# LEDS.net
KiCad netlist of a schematic drawn in Altium Designer
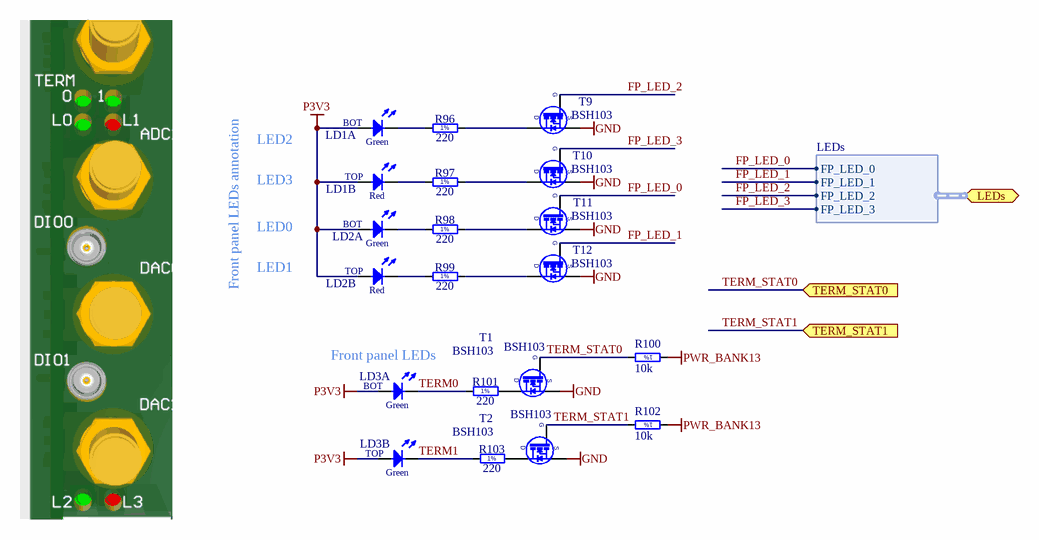
[diagram p0: LEDS.SchDoc]

(export (version "E")
  (design (tool "Eeschema 10.0.6"))
  (components
    (comp (ref "LD1")
      (value "Red/Green")
      (footprint "LED_DIALIGHT_571-0112F")
      (description "2x LED  Botom Green, Top Red")
      (fields
        (field (name "PART NUMBER") "LED_DIALIGHT_571-0112F")
        (field (name "MANUFACTURER") "DIALIGHT")
        (field (name "AUTHOR") "CERN DEM JLC")
      )
      (libsource (lib "ICs And Semiconductors") (part "LED x2 G-1C2A-BOT_R-3C4A-TOP"))
    )
    (comp (ref "LD2")
      (value "Red/Green")
      (footprint "LED_DIALIGHT_571-0112F")
      (description "2x LED  Botom Green, Top Red")
      (fields
        (field (name "PART NUMBER") "LED_DIALIGHT_571-0112F")
        (field (name "MANUFACTURER") "DIALIGHT")
        (field (name "AUTHOR") "CERN DEM JLC")
      )
      (libsource (lib "ICs And Semiconductors") (part "LED x2 G-1C2A-BOT_R-3C4A-TOP"))
    )
    (comp (ref "LD3")
      (value "Green/Green")
      (footprint "LED_DIALIGHT_571-0122F")
      (description "LED x2 Green 1C2A-BOT_3C4A-TOP")
      (fields
        (field (name "PART NUMBER") "LED_DIALIGHT_571-0122F")
        (field (name "MANUFACTURER") "DIALIGHT")
        (field (name "AUTHOR") "CERN DEM JLC")
      )
      (libsource (lib "ICs And Semiconductors") (part "LED x2 Green 1C2A-BOT_3C4A-TOP"))
    )
    (comp (ref "R96")
      (value "220")
      (footprint "RESC1608X55N")
      (description "Resistor - 1%")
      (fields
        (field (name "PART NUMBER") "R0603_220R_1%_0.1W_100PPM")
        (field (name "POWER") "0.1W")
        (field (name "AUTHOR") "CERN DEM JLC")
      )
      (libsource (lib "Resistors") (part "Resistor - 1%"))
    )
    (comp (ref "R97")
      (value "220")
      (footprint "RESC1608X55N")
      (description "Resistor - 1%")
      (fields
        (field (name "PART NUMBER") "R0603_220R_1%_0.1W_100PPM")
        (field (name "POWER") "0.1W")
        (field (name "AUTHOR") "CERN DEM JLC")
      )
      (libsource (lib "Resistors") (part "Resistor - 1%"))
    )
    (comp (ref "R98")
      (value "220")
      (footprint "RESC1608X55N")
      (description "Resistor - 1%")
      (fields
        (field (name "PART NUMBER") "R0603_220R_1%_0.1W_100PPM")
        (field (name "POWER") "0.1W")
        (field (name "AUTHOR") "CERN DEM JLC")
      )
      (libsource (lib "Resistors") (part "Resistor - 1%"))
    )
    (comp (ref "R99")
      (value "220")
      (footprint "RESC1608X55N")
      (description "Resistor - 1%")
      (fields
        (field (name "PART NUMBER") "R0603_220R_1%_0.1W_100PPM")
        (field (name "POWER") "0.1W")
        (field (name "AUTHOR") "CERN DEM JLC")
      )
      (libsource (lib "Resistors") (part "Resistor - 1%"))
    )
    (comp (ref "R100")
      (value "10k")
      (footprint "RESC1005X40N")
      (description "Resistor - 1%")
      (fields
        (field (name "PART NUMBER") "R0402_10K_1%_0.0625W_100PPM")
        (field (name "POWER") "0.0625W")
        (field (name "AUTHOR") "CERN DEM JLC")
      )
      (libsource (lib "Resistors") (part "Resistor - 1%"))
    )
    (comp (ref "R101")
      (value "220")
      (footprint "RESC1608X55N")
      (description "Resistor - 1%")
      (fields
        (field (name "PART NUMBER") "R0603_220R_1%_0.1W_100PPM")
        (field (name "POWER") "0.1W")
        (field (name "AUTHOR") "CERN DEM JLC")
      )
      (libsource (lib "Resistors") (part "Resistor - 1%"))
    )
    (comp (ref "R102")
      (value "10k")
      (footprint "RESC1005X40N")
      (description "Resistor - 1%")
      (fields
        (field (name "PART NUMBER") "R0402_10K_1%_0.0625W_100PPM")
        (field (name "POWER") "0.0625W")
        (field (name "AUTHOR") "CERN DEM JLC")
      )
      (libsource (lib "Resistors") (part "Resistor - 1%"))
    )
    (comp (ref "R103")
      (value "220")
      (footprint "RESC1608X55N")
      (description "Resistor - 1%")
      (fields
        (field (name "PART NUMBER") "R0603_220R_1%_0.1W_100PPM")
        (field (name "POWER") "0.1W")
        (field (name "AUTHOR") "CERN DEM JLC")
      )
      (libsource (lib "Resistors") (part "Resistor - 1%"))
    )
    (comp (ref "T1")
      (value "BSH103")
      (footprint "SOT95P230X110-3N")
      (description "N-CHANNEL MOSFET WITH DIODE")
      (fields
        (field (name "PART NUMBER") "BSH103")
        (field (name "MANUFACTURER") "NEXPERIA")
        (field (name "AUTHOR") "CERN DEM JLC")
      )
      (libsource (lib "ICs And Semiconductors") (part "N-MOSFET-D 1G 2S 3D"))
    )
    (comp (ref "T2")
      (value "BSH103")
      (footprint "SOT95P230X110-3N")
      (description "N-CHANNEL MOSFET WITH DIODE")
      (fields
        (field (name "PART NUMBER") "BSH103")
        (field (name "MANUFACTURER") "NEXPERIA")
        (field (name "AUTHOR") "CERN DEM JLC")
      )
      (libsource (lib "ICs And Semiconductors") (part "N-MOSFET-D 1G 2S 3D"))
    )
    (comp (ref "T9")
      (value "BSH103")
      (footprint "SOT95P230X110-3N")
      (description "N-CHANNEL MOSFET WITH DIODE")
      (fields (field (name "MANUFACTURER") "NEXPERIA") (field (name "AUTHOR") "CERN DEM JLC"))
      (libsource (lib "ICs And Semiconductors") (part "N-MOSFET-D 1G 2S 3D"))
    )
    (comp (ref "T10")
      (value "BSH103")
      (footprint "SOT95P230X110-3N")
      (description "N-CHANNEL MOSFET WITH DIODE")
      (fields (field (name "MANUFACTURER") "NEXPERIA") (field (name "AUTHOR") "CERN DEM JLC"))
      (libsource (lib "ICs And Semiconductors") (part "N-MOSFET-D 1G 2S 3D"))
    )
    (comp (ref "T11")
      (value "BSH103")
      (footprint "SOT95P230X110-3N")
      (description "N-CHANNEL MOSFET WITH DIODE")
      (fields (field (name "MANUFACTURER") "NEXPERIA") (field (name "AUTHOR") "CERN DEM JLC"))
      (libsource (lib "ICs And Semiconductors") (part "N-MOSFET-D 1G 2S 3D"))
    )
    (comp (ref "T12")
      (value "BSH103")
      (footprint "SOT95P230X110-3N")
      (description "N-CHANNEL MOSFET WITH DIODE")
      (fields (field (name "MANUFACTURER") "NEXPERIA") (field (name "AUTHOR") "CERN DEM JLC"))
      (libsource (lib "ICs And Semiconductors") (part "N-MOSFET-D 1G 2S 3D"))
    )
  )
  (nets
    (net (code "2") (name "/FP_LED_0") (class "Default")
      (node (ref "T11") (pin "1") (pinfunction "G_1") (pintype "passive"))
    )
    (net (code "3") (name "/FP_LED_1") (class "Default")
      (node (ref "T12") (pin "1") (pinfunction "G_1") (pintype "passive"))
    )
    (net (code "4") (name "/FP_LED_2") (class "Default")
      (node (ref "T9") (pin "1") (pinfunction "G_1") (pintype "passive"))
    )
    (net (code "5") (name "/FP_LED_3") (class "Default")
      (node (ref "T10") (pin "1") (pinfunction "G_1") (pintype "passive"))
    )
    (net (code "6") (name "/TERM0") (class "Default")
      (node (ref "LD3") (pin "1") (pinfunction "C_1") (pintype "passive"))
      (node (ref "R101") (pin "1") (pinfunction "1_1") (pintype "passive"))
    )
    (net (code "7") (name "/TERM1") (class "Default")
      (node (ref "LD3") (pin "3") (pinfunction "C_3") (pintype "passive"))
      (node (ref "R103") (pin "1") (pinfunction "1_1") (pintype "passive"))
    )
    (net (code "8") (name "/TERM_STAT0") (class "Default")
      (node (ref "R100") (pin "2") (pinfunction "2_2") (pintype "passive"))
      (node (ref "T1") (pin "1") (pinfunction "G_1") (pintype "passive"))
    )
    (net (code "9") (name "/TERM_STAT1") (class "Default")
      (node (ref "R102") (pin "2") (pinfunction "2_2") (pintype "passive"))
      (node (ref "T2") (pin "1") (pinfunction "G_1") (pintype "passive"))
    )
    (net (code "11") (name "GND") (class "Default")
      (node (ref "T1") (pin "2") (pinfunction "S_2") (pintype "passive"))
      (node (ref "T10") (pin "2") (pinfunction "S_2") (pintype "passive"))
      (node (ref "T11") (pin "2") (pinfunction "S_2") (pintype "passive"))
      (node (ref "T12") (pin "2") (pinfunction "S_2") (pintype "passive"))
      (node (ref "T2") (pin "2") (pinfunction "S_2") (pintype "passive"))
      (node (ref "T9") (pin "2") (pinfunction "S_2") (pintype "passive"))
    )
    (net (code "12") (name "Net-(LD1A-C)") (class "Default")
      (node (ref "LD1") (pin "1") (pinfunction "C_1") (pintype "passive"))
      (node (ref "R96") (pin "1") (pinfunction "1_1") (pintype "passive"))
    )
    (net (code "13") (name "Net-(LD1B-C)") (class "Default")
      (node (ref "LD1") (pin "3") (pinfunction "C_3") (pintype "passive"))
      (node (ref "R97") (pin "1") (pinfunction "1_1") (pintype "passive"))
    )
    (net (code "14") (name "Net-(LD2A-C)") (class "Default")
      (node (ref "LD2") (pin "1") (pinfunction "C_1") (pintype "passive"))
      (node (ref "R98") (pin "1") (pinfunction "1_1") (pintype "passive"))
    )
    (net (code "15") (name "Net-(LD2B-C)") (class "Default")
      (node (ref "LD2") (pin "3") (pinfunction "C_3") (pintype "passive"))
      (node (ref "R99") (pin "1") (pinfunction "1_1") (pintype "passive"))
    )
    (net (code "16") (name "Net-(T1-D)") (class "Default")
      (node (ref "R101") (pin "2") (pinfunction "2_2") (pintype "passive"))
      (node (ref "T1") (pin "3") (pinfunction "D_3") (pintype "passive"))
    )
    (net (code "17") (name "Net-(T2-D)") (class "Default")
      (node (ref "R103") (pin "2") (pinfunction "2_2") (pintype "passive"))
      (node (ref "T2") (pin "3") (pinfunction "D_3") (pintype "passive"))
    )
    (net (code "18") (name "Net-(T9-D)") (class "Default")
      (node (ref "R96") (pin "2") (pinfunction "2_2") (pintype "passive"))
      (node (ref "T9") (pin "3") (pinfunction "D_3") (pintype "passive"))
    )
    (net (code "19") (name "Net-(T10-D)") (class "Default")
      (node (ref "R97") (pin "2") (pinfunction "2_2") (pintype "passive"))
      (node (ref "T10") (pin "3") (pinfunction "D_3") (pintype "passive"))
    )
    (net (code "20") (name "Net-(T11-D)") (class "Default")
      (node (ref "R98") (pin "2") (pinfunction "2_2") (pintype "passive"))
      (node (ref "T11") (pin "3") (pinfunction "D_3") (pintype "passive"))
    )
    (net (code "21") (name "Net-(T12-D)") (class "Default")
      (node (ref "R99") (pin "2") (pinfunction "2_2") (pintype "passive"))
      (node (ref "T12") (pin "3") (pinfunction "D_3") (pintype "passive"))
    )
    (net (code "22") (name "P3V3") (class "Default")
      (node (ref "LD1") (pin "2") (pinfunction "A_2") (pintype "passive"))
      (node (ref "LD1") (pin "4") (pinfunction "A_4") (pintype "passive"))
      (node (ref "LD2") (pin "2") (pinfunction "A_2") (pintype "passive"))
      (node (ref "LD2") (pin "4") (pinfunction "A_4") (pintype "passive"))
      (node (ref "LD3") (pin "2") (pinfunction "A_2") (pintype "passive"))
      (node (ref "LD3") (pin "4") (pinfunction "A_4") (pintype "passive"))
    )
    (net (code "23") (name "PWR_BANK13") (class "Default")
      (node (ref "R100") (pin "1") (pinfunction "1_1") (pintype "passive"))
      (node (ref "R102") (pin "1") (pinfunction "1_1") (pintype "passive"))
    )
  )
)
